# e-ink_display.net
KiCad netlist of a schematic drawn in Altium Designer
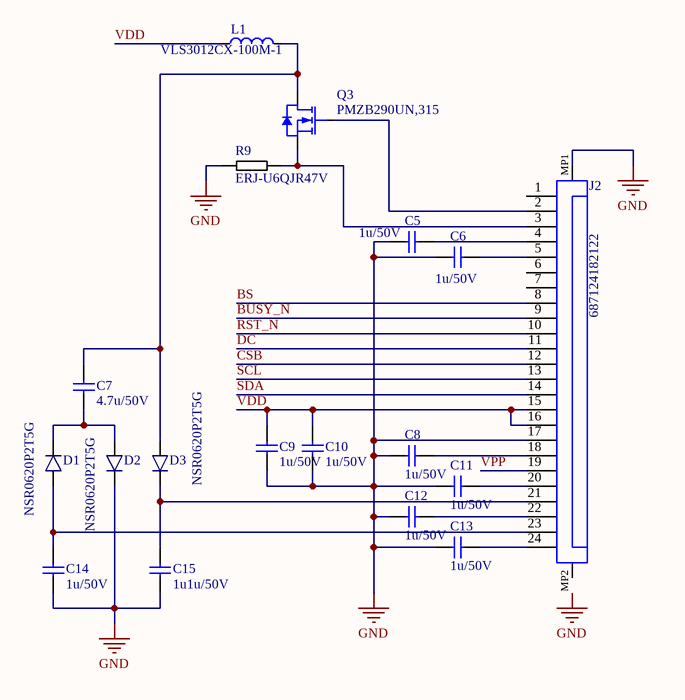
[diagram p0: e-ink_display.SchDoc]

(export (version "E")
  (design (tool "Eeschema 10.0.6"))
  (components
    (comp (ref "C5") (value "1u/50V") (footprint "CAPC1005X04L") (libsource (lib "Schlib1") (part "C0402")))
    (comp (ref "C6") (value "1u/50V") (footprint "CAPC1005X04L") (libsource (lib "Schlib1") (part "C0402")))
    (comp (ref "C7") (value "4.7u/50V") (footprint "CAPC1005X04L") (libsource (lib "Schlib1") (part "C0402")))
    (comp (ref "C8") (value "1u/50V") (footprint "CAPC1005X04L") (libsource (lib "Schlib1") (part "C0402")))
    (comp (ref "C9") (value "1u/50V") (footprint "CAPC1005X04L") (libsource (lib "Schlib1") (part "C0402")))
    (comp (ref "C10") (value "1u/50V") (footprint "CAPC1005X04L") (libsource (lib "Schlib1") (part "C0402")))
    (comp (ref "C11") (value "1u/50V") (footprint "CAPC1005X04L") (libsource (lib "Schlib1") (part "C0402")))
    (comp (ref "C12") (value "1u/50V") (footprint "CAPC1005X04L") (libsource (lib "Schlib1") (part "C0402")))
    (comp (ref "C13") (value "1u/50V") (footprint "CAPC1005X04L") (libsource (lib "Schlib1") (part "C0402")))
    (comp (ref "C14") (value "1u/50V") (footprint "CAPC1005X04L") (libsource (lib "Schlib1") (part "C0402")))
    (comp (ref "C15")
      (value "1u1u/50V")
      (footprint "CAPC1005X04L")
      (libsource (lib "Schlib1") (part "C0402"))
    )
    (comp (ref "D1")
      (value "NSR0620P2T5G")
      (footprint "SODFL100X40-2N")
      (description "20V schottky barrier diode, Vf 350 mV @ 100 mA, Ir 2.0 µA @ 10 V, If 500 mA")
      (fields (field (name "MANUFACTURER") "ON Semiconductor"))
      (libsource (lib "Schlib1") (part "NSR0620P2T5G"))
    )
    (comp (ref "D2")
      (value "NSR0620P2T5G")
      (footprint "SODFL100X40-2N")
      (description "20V schottky barrier diode, Vf 350 mV @ 100 mA, Ir 2.0 µA @ 10 V, If 500 mA")
      (fields (field (name "MANUFACTURER") "ON Semiconductor"))
      (libsource (lib "Schlib1") (part "NSR0620P2T5G"))
    )
    (comp (ref "D3")
      (value "NSR0620P2T5G")
      (footprint "SODFL100X40-2N")
      (description "20V schottky barrier diode, Vf 350 mV @ 100 mA, Ir 2.0 µA @ 10 V, If 500 mA")
      (fields (field (name "MANUFACTURER") "ON Semiconductor"))
      (libsource (lib "Schlib1") (part "NSR0620P2T5G"))
    )
    (comp (ref "J2")
      (value "687124182122")
      (footprint "687124182122")
      (description "WR-FPC SMT ZIF Horizontal Dual Contact, pitch 0.5mm, 24p")
      (fields (field (name "MANUFACTURER") "Wurth Elektronik"))
      (libsource (lib "Schlib1") (part "687124182122"))
    )
    (comp (ref "L1")
      (value "VLS3012CX-100M-1")
      (footprint "VLS3012CX-100M-1")
      (description "Inductor Power Shielded Wirewound 10uH 20% 1MHz Ferrite 1.12A 0.324Ohm DCR 1212 T/R")
      (fields (field (name "MANUFACTURER") "TDK") (field (name "TOLERANCE") "20%"))
      (libsource (lib "Schlib1") (part "VLS3012CX-100M-1"))
    )
    (comp (ref "Q3")
      (value "PMZB290UN,315")
      (footprint "NXP-SOT883B_N")
      (description "PMZB290UN - 20 V, single N-channel Trench MOSFET")
      (fields (field (name "MANUFACTURER") "NXP Semiconductors"))
      (libsource (lib "Schlib1") (part "PMZB290UN,315"))
    )
    (comp (ref "R9")
      (value "ERJ-U6QJR47V")
      (footprint "R0805")
      (description "Anti-Sulfurated Thick Film Chip Resistors, 0.47½, 5%, 0.25W")
      (fields (field (name "MANUFACTURER") "Panasonic") (field (name "TOLERANCE") "5%"))
      (libsource (lib "Schlib1") (part "ERJ-U6QJR47V"))
    )
  )
  (nets
    (net (code "1") (name "/BS") (class "Default")
      (node (ref "J2") (pin "8") (pinfunction "8_8") (pintype "passive"))
    )
    (net (code "2") (name "/BUSY_N") (class "Default")
      (node (ref "J2") (pin "9") (pinfunction "9_9") (pintype "passive"))
    )
    (net (code "3") (name "/CSB") (class "Default")
      (node (ref "J2") (pin "12") (pinfunction "12_12") (pintype "passive"))
    )
    (net (code "4") (name "/DC") (class "Default")
      (node (ref "J2") (pin "11") (pinfunction "11_11") (pintype "passive"))
    )
    (net (code "5") (name "/RST_N") (class "Default")
      (node (ref "J2") (pin "10") (pinfunction "10_10") (pintype "passive"))
    )
    (net (code "6") (name "/SCL") (class "Default")
      (node (ref "J2") (pin "13") (pinfunction "13_13") (pintype "passive"))
    )
    (net (code "7") (name "/SDA") (class "Default")
      (node (ref "J2") (pin "14") (pinfunction "14_14") (pintype "passive"))
    )
    (net (code "8") (name "/VDD") (class "Default")
      (node (ref "C10") (pin "2") (pinfunction "2_2") (pintype "passive"))
      (node (ref "C9") (pin "2") (pinfunction "2_2") (pintype "passive"))
      (node (ref "J2") (pin "15") (pinfunction "15_15") (pintype "passive"))
      (node (ref "J2") (pin "16") (pinfunction "16_16") (pintype "passive"))
      (node (ref "L1") (pin "1") (pinfunction "1_1") (pintype "passive"))
    )
    (net (code "9") (name "/VPP") (class "Default")
      (node (ref "J2") (pin "19") (pinfunction "19_19") (pintype "passive"))
    )
    (net (code "10") (name "GND") (class "Default")
      (node (ref "C10") (pin "1") (pinfunction "1_1") (pintype "passive"))
      (node (ref "C11") (pin "1") (pinfunction "1_1") (pintype "passive"))
      (node (ref "C12") (pin "1") (pinfunction "1_1") (pintype "passive"))
      (node (ref "C13") (pin "1") (pinfunction "1_1") (pintype "passive"))
      (node (ref "C14") (pin "1") (pinfunction "1_1") (pintype "passive"))
      (node (ref "C15") (pin "1") (pinfunction "1_1") (pintype "passive"))
      (node (ref "C5") (pin "1") (pinfunction "1_1") (pintype "passive"))
      (node (ref "C6") (pin "1") (pinfunction "1_1") (pintype "passive"))
      (node (ref "C8") (pin "1") (pinfunction "1_1") (pintype "passive"))
      (node (ref "C9") (pin "1") (pinfunction "1_1") (pintype "passive"))
      (node (ref "D2") (pin "1") (pinfunction "C_1") (pintype "passive"))
      (node (ref "J2") (pin "17") (pinfunction "17_17") (pintype "passive"))
      (node (ref "J2") (pin "MP1") (pinfunction "MP1_MP1") (pintype "passive"))
      (node (ref "R9") (pin "1") (pinfunction "1_1") (pintype "passive"))
    )
    (net (code "11") (name "Net-(C5-Pad2)") (class "Default")
      (node (ref "C5") (pin "2") (pinfunction "2_2") (pintype "passive"))
      (node (ref "J2") (pin "4") (pinfunction "4_4") (pintype "passive"))
    )
    (net (code "12") (name "Net-(C6-Pad2)") (class "Default")
      (node (ref "C6") (pin "2") (pinfunction "2_2") (pintype "passive"))
      (node (ref "J2") (pin "5") (pinfunction "5_5") (pintype "passive"))
    )
    (net (code "13") (name "Net-(C8-Pad2)") (class "Default")
      (node (ref "C8") (pin "2") (pinfunction "2_2") (pintype "passive"))
      (node (ref "J2") (pin "18") (pinfunction "18_18") (pintype "passive"))
    )
    (net (code "14") (name "Net-(C11-Pad2)") (class "Default")
      (node (ref "C11") (pin "2") (pinfunction "2_2") (pintype "passive"))
      (node (ref "J2") (pin "20") (pinfunction "20_20") (pintype "passive"))
    )
    (net (code "15") (name "Net-(C12-Pad2)") (class "Default")
      (node (ref "C12") (pin "2") (pinfunction "2_2") (pintype "passive"))
      (node (ref "J2") (pin "22") (pinfunction "22_22") (pintype "passive"))
    )
    (net (code "16") (name "Net-(C13-Pad2)") (class "Default")
      (node (ref "C13") (pin "2") (pinfunction "2_2") (pintype "passive"))
      (node (ref "J2") (pin "24") (pinfunction "24_24") (pintype "passive"))
    )
    (net (code "17") (name "Net-(D1-A)") (class "Default")
      (node (ref "C14") (pin "2") (pinfunction "2_2") (pintype "passive"))
      (node (ref "D1") (pin "2") (pinfunction "A_2") (pintype "passive"))
      (node (ref "J2") (pin "23") (pinfunction "23_23") (pintype "passive"))
    )
    (net (code "18") (name "Net-(D1-C)") (class "Default")
      (node (ref "C7") (pin "1") (pinfunction "1_1") (pintype "passive"))
      (node (ref "D1") (pin "1") (pinfunction "C_1") (pintype "passive"))
      (node (ref "D2") (pin "2") (pinfunction "A_2") (pintype "passive"))
    )
    (net (code "19") (name "Net-(D3-A)") (class "Default")
      (node (ref "C7") (pin "2") (pinfunction "2_2") (pintype "passive"))
      (node (ref "D3") (pin "2") (pinfunction "A_2") (pintype "passive"))
      (node (ref "L1") (pin "2") (pinfunction "2_2") (pintype "passive"))
      (node (ref "Q3") (pin "3") (pinfunction "D_3") (pintype "passive"))
    )
    (net (code "20") (name "Net-(D3-C)") (class "Default")
      (node (ref "C15") (pin "2") (pinfunction "2_2") (pintype "passive"))
      (node (ref "D3") (pin "1") (pinfunction "C_1") (pintype "passive"))
      (node (ref "J2") (pin "21") (pinfunction "21_21") (pintype "passive"))
    )
    (net (code "21") (name "Net-(Q3-G)") (class "Default")
      (node (ref "J2") (pin "2") (pinfunction "2_2") (pintype "passive"))
      (node (ref "Q3") (pin "1") (pinfunction "G_1") (pintype "passive"))
    )
    (net (code "22") (name "Net-(Q3-S)") (class "Default")
      (node (ref "J2") (pin "3") (pinfunction "3_3") (pintype "passive"))
      (node (ref "Q3") (pin "2") (pinfunction "S_2") (pintype "passive"))
      (node (ref "R9") (pin "1") (pinfunction "1_1") (pintype "passive"))
    )
    (net (code "23") (name "unconnected-(J2-Pad1)") (class "Default")
      (node (ref "J2") (pin "1") (pinfunction "1_1") (pintype "passive"))
    )
    (net (code "24") (name "unconnected-(J2-Pad6)") (class "Default")
      (node (ref "J2") (pin "6") (pinfunction "6_6") (pintype "passive"))
    )
    (net (code "25") (name "unconnected-(J2-Pad7)") (class "Default")
      (node (ref "J2") (pin "7") (pinfunction "7_7") (pintype "passive"))
    )
    (net (code "26") (name "unconnected-(J2-PadMP2)") (class "Default")
      (node (ref "J2") (pin "MP2") (pinfunction "MP2_MP2") (pintype "passive"))
    )
  )
)
